# Pump_Drive.net
KiCad netlist of a schematic drawn in Altium Designer
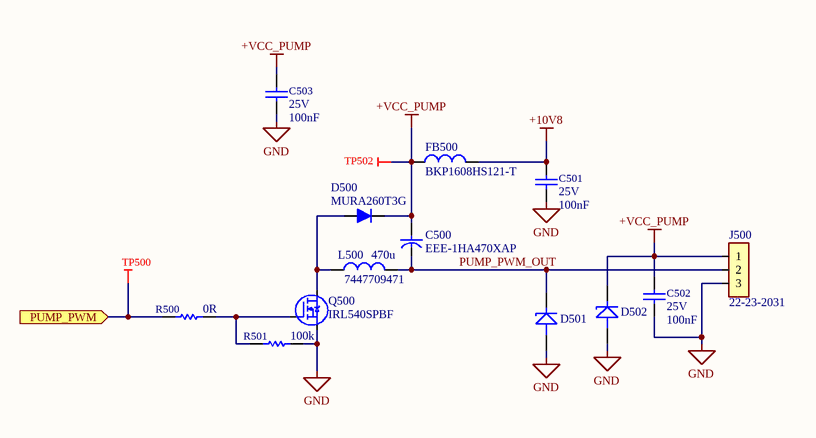
[diagram p0: Pump Drive.SchDoc]

(export (version "E")
  (design (tool "Eeschema 10.0.6"))
  (components
    (comp (ref "C500")
      (value "EEE-1HA470XAP")
      (footprint "Panasonic S-V D8")
      (description "CAP ALUM 47UF 20% 50V SMD")
      (fields (field (name "MANUFACTURER") "Panasonic"))
      (libsource (lib "Gas Monitor Components") (part "EEE-1HA470XAP"))
    )
    (comp (ref "C501")
      (value "100nF")
      (footprint "CAPC1005X06N")
      (fields
        (field (name "VOLTAGE") "25V")
        (field (name "MANUFACTURER PART NUMBER") "CL05A104KA5NNNC")
        (field (name "MANUFACTURER") "Samsung")
        (field (name "Comment") "4.7uF")
      )
      (libsource (lib "Capacitors") (part "4.7uF_0603_10V"))
    )
    (comp (ref "C502")
      (value "100nF")
      (footprint "CAPC1005X06N")
      (fields
        (field (name "VOLTAGE") "25V")
        (field (name "MANUFACTURER PART NUMBER") "CL05A104KA5NNNC")
        (field (name "MANUFACTURER") "Samsung")
        (field (name "Comment") "4.7uF")
      )
      (libsource (lib "Capacitors") (part "4.7uF_0603_10V"))
    )
    (comp (ref "C503")
      (value "100nF")
      (footprint "CAPC1005X06N")
      (fields
        (field (name "VOLTAGE") "25V")
        (field (name "MANUFACTURER PART NUMBER") "CL05A104KA5NNNC")
        (field (name "MANUFACTURER") "Samsung")
        (field (name "Comment") "4.7uF")
      )
      (libsource (lib "Capacitors") (part "4.7uF_0603_10V"))
    )
    (comp (ref "D500")
      (value "MURA260T3G")
      (footprint "Diode SMA DIOM5226X240N")
      (description "Diode Standard 600V 2A Surface Mount SMA")
      (fields (field (name "MANUFACTURER") "ON Semi") (field (name "MANUFACTURER PART NUMBER") "MURA260T3G"))
      (libsource (lib "Gas Monitor Components") (part "MURA260T3G"))
    )
    (comp (ref "D501")
      (value "12V TVS")
      (footprint "NXP PTVSxS1UR-Series (SOD123W)")
      (fields
        (field (name "MANUFACTURER") "Nexperia")
        (field (name "MANUFACTURER PART NUMBER") "PTVS12VS1UR,115")
      )
      (libsource (lib "FSM_2018") (part "NXP PTVSxS1UR-Series"))
    )
    (comp (ref "D502")
      (value "12V TVS")
      (footprint "NXP PTVSxS1UR-Series (SOD123W)")
      (fields
        (field (name "MANUFACTURER") "Nexperia")
        (field (name "MANUFACTURER PART NUMBER") "PTVS12VS1UR,115")
      )
      (libsource (lib "FSM_2018") (part "NXP PTVSxS1UR-Series"))
    )
    (comp (ref "FB500")
      (value "BKP1608HS121-T")
      (footprint "RESC1608X06N")
      (description "120 Ohms @ 100MHz 1 Power Line Ferrite Bead 0603 (1608 Metric) 2.7A 35mOhm")
      (fields (field (name "MANUFACTURER") "Taiyo Yuden"))
      (libsource (lib "Gas Monitor Components") (part "BKP1608HS121-T"))
    )
    (comp (ref "J500")
      (value "22-23-2031")
      (footprint "22-23-2031")
      (description "Connector Header Through Hole 3 position 0.100\" (2.54mm)")
      (fields (field (name "MANUFACTURER") "Molex") (field (name "MANUFACTURER PART NUMBER") "0022232031"))
      (libsource (lib "Gas Monitor Components") (part "22-23-2031"))
    )
    (comp (ref "L500")
      (value "7447709471")
      (footprint "WE-PD 1210")
      (description "470µH Shielded Wirewound Inductor 1.4A 560mOhm Max Nonstandard")
      (fields (field (name "MANUFACTURER") "Wurth Electronics") (field (name "ALTIUM_VALUE") "470u"))
      (libsource (lib "Gas Monitor Components") (part "7447709471"))
    )
    (comp (ref "Q500")
      (value "IRL540SPBF")
      (footprint "D2PAK")
      (description "MOSFET N-CH 100V 28A D2PAK")
      (fields (field (name "MANUFACTURER") "Vishay Siliconix"))
      (libsource (lib "Gas Monitor Components") (part "IRL540SPBF"))
    )
    (comp (ref "R500")
      (value "0R")
      (footprint "RESC1608X06N")
      (fields
        (field (name "MANUFACTURER") "Panasonic")
        (field (name "MANUFACTURER PART NUMBER") "ERJ-3GEY0R00V")
        (field (name "Comment") "RES: GENERAL")
      )
      (libsource (lib "Santuary") (part "RES{colon} GENERAL"))
    )
    (comp (ref "R501")
      (value "100k")
      (footprint "RESC1608X06N")
      (fields
        (field (name "MANUFACTURER") "Panasonic")
        (field (name "MANUFACTURER PART NUMBER") "ERJ-3GEYJ104V")
        (field (name "Comment") "RES: GENERAL")
      )
      (libsource (lib "Santuary") (part "RES{colon} GENERAL"))
    )
    (comp (ref "TP500")
      (value "PAD")
      (footprint "TP_SMD_39MIL")
      (description "SMD Test Pad")
      (fields (field (name "MANUFACTURER") "No P/N Required"))
      (libsource (lib "Connectors") (part "TP_SMD_39MIL"))
    )
    (comp (ref "TP502")
      (value "PAD")
      (footprint "TP_SMD_39MIL")
      (description "SMD Test Pad")
      (fields (field (name "MANUFACTURER") "No P/N Required"))
      (libsource (lib "Connectors") (part "TP_SMD_39MIL"))
    )
  )
  (nets
    (net (code "1") (name "+10V8") (class "Default")
      (node (ref "C501") (pin "1") (pintype "passive"))
      (node (ref "FB500") (pin "2") (pintype "passive"))
    )
    (net (code "2") (name "+VCC_PUMP") (class "Default")
      (node (ref "C500") (pin "1") (pintype "passive"))
      (node (ref "C502") (pin "1") (pintype "passive"))
      (node (ref "C503") (pin "1") (pintype "passive"))
      (node (ref "D500") (pin "1") (pinfunction "K_1") (pintype "passive"))
      (node (ref "D502") (pin "1") (pinfunction "1_1") (pintype "passive"))
      (node (ref "FB500") (pin "1") (pintype "passive"))
      (node (ref "J500") (pin "1") (pinfunction "1_1") (pintype "passive"))
      (node (ref "TP502") (pin "1") (pintype "passive"))
    )
    (net (code "3") (name "/PUMP_PWM") (class "Default")
      (node (ref "R500") (pin "2") (pinfunction "2_2") (pintype "passive"))
      (node (ref "TP500") (pin "1") (pintype "passive"))
    )
    (net (code "4") (name "/PUMP_PWM_OUT") (class "Default")
      (node (ref "C500") (pin "2") (pintype "passive"))
      (node (ref "D501") (pin "1") (pinfunction "1_1") (pintype "passive"))
      (node (ref "J500") (pin "2") (pinfunction "2_2") (pintype "passive"))
      (node (ref "L500") (pin "2") (pintype "passive"))
    )
    (net (code "5") (name "GND") (class "Default")
      (node (ref "C501") (pin "2") (pintype "passive"))
      (node (ref "C502") (pin "2") (pintype "passive"))
      (node (ref "C503") (pin "2") (pintype "passive"))
      (node (ref "D501") (pin "2") (pinfunction "2_2") (pintype "passive"))
      (node (ref "D502") (pin "2") (pinfunction "2_2") (pintype "passive"))
      (node (ref "J500") (pin "3") (pinfunction "3_3") (pintype "passive"))
      (node (ref "Q500") (pin "3") (pinfunction "S_3") (pintype "passive"))
      (node (ref "R501") (pin "1") (pinfunction "1_1") (pintype "passive"))
    )
    (net (code "6") (name "Net-(D500-A)") (class "Default")
      (node (ref "D500") (pin "2") (pinfunction "A_2") (pintype "passive"))
      (node (ref "L500") (pin "1") (pintype "passive"))
      (node (ref "Q500") (pin "2") (pinfunction "D_2") (pintype "passive"))
    )
    (net (code "7") (name "Net-(Q500-G)") (class "Default")
      (node (ref "Q500") (pin "1") (pinfunction "G_1") (pintype "passive"))
      (node (ref "R500") (pin "1") (pinfunction "1_1") (pintype "passive"))
      (node (ref "R501") (pin "2") (pinfunction "2_2") (pintype "passive"))
    )
  )
)
